# sparkfun-samd21-pro-breakout.net
KiCad netlist of a schematic drawn in EAGLE
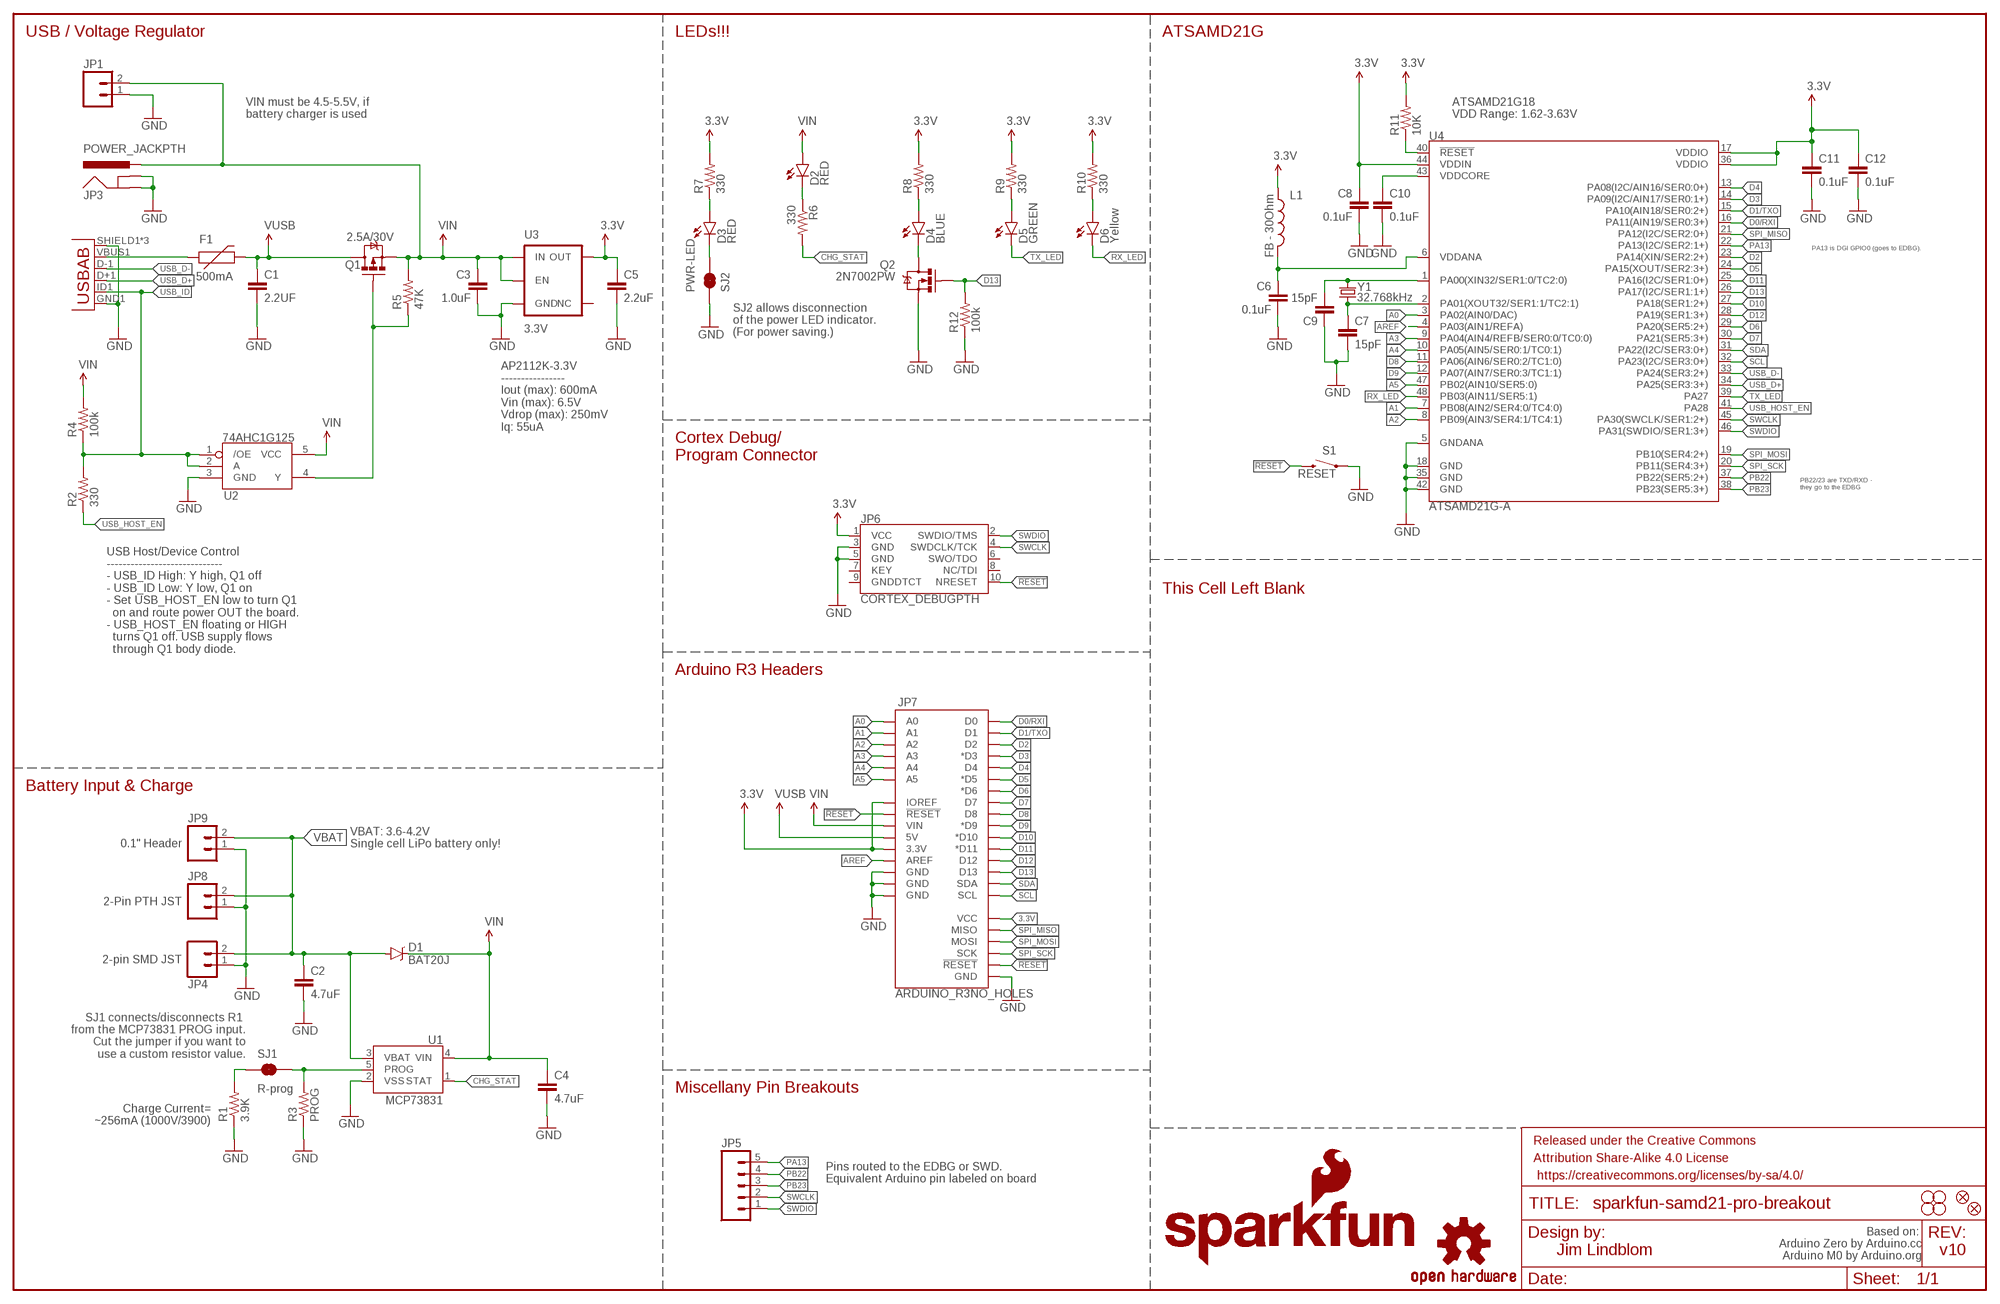
[diagram p0: schematic, sheet 1]

(export (version "E")
  (design (tool "Eeschema 10.0.6"))
  (components
    (comp (ref "C1")
      (value "2.2UF")
      (footprint "eagle-import:1206")
      (libsource (lib "eagle-import") (part "2.2UF50V10%(1206)"))
    )
    (comp (ref "C2")
      (value "4.7uF")
      (footprint "eagle-import:0603-CAP")
      (libsource (lib "eagle-import") (part "4.7UF-6.3V-10%(0603)0603"))
    )
    (comp (ref "C3")
      (value "1.0uF")
      (footprint "eagle-import:0805-CAP")
      (libsource (lib "eagle-import") (part "1.0UF-25V-+80/-20(0805){dblquote}"))
    )
    (comp (ref "C4")
      (value "4.7uF")
      (footprint "eagle-import:0603-CAP")
      (libsource (lib "eagle-import") (part "4.7UF-6.3V-10%(0603)0603"))
    )
    (comp (ref "C5")
      (value "2.2uF")
      (footprint "eagle-import:0603-CAP")
      (libsource (lib "eagle-import") (part "2.2UF-10V-20%(0603)"))
    )
    (comp (ref "C6")
      (value "0.1uF")
      (footprint "eagle-import:0603-CAP")
      (libsource (lib "eagle-import") (part "0.1UF-25V(+80/-20%)(0603)"))
    )
    (comp (ref "C7")
      (value "15pF")
      (footprint "eagle-import:0603-CAP")
      (libsource (lib "eagle-import") (part "15PF-50V-5%(0603)"))
    )
    (comp (ref "C8")
      (value "0.1uF")
      (footprint "eagle-import:0603-CAP")
      (libsource (lib "eagle-import") (part "0.1UF-25V(+80/-20%)(0603)"))
    )
    (comp (ref "C9")
      (value "15pF")
      (footprint "eagle-import:0603-CAP")
      (libsource (lib "eagle-import") (part "15PF-50V-5%(0603)"))
    )
    (comp (ref "C10")
      (value "0.1uF")
      (footprint "eagle-import:0603-CAP")
      (libsource (lib "eagle-import") (part "0.1UF-25V(+80/-20%)(0603)"))
    )
    (comp (ref "C11")
      (value "0.1uF")
      (footprint "eagle-import:0603-CAP")
      (libsource (lib "eagle-import") (part "0.1UF-25V(+80/-20%)(0603)"))
    )
    (comp (ref "C12")
      (value "0.1uF")
      (footprint "eagle-import:0603-CAP")
      (libsource (lib "eagle-import") (part "0.1UF-25V(+80/-20%)(0603)"))
    )
    (comp (ref "D1")
      (value "BAT20J")
      (footprint "eagle-import:SOD-323")
      (libsource (lib "eagle-import") (part "DIODE-SCHOTTKY-BAT20J"))
    )
    (comp (ref "D2")
      (value "RED")
      (footprint "eagle-import:LED-0603")
      (libsource (lib "eagle-import") (part "LED-RED0603"))
    )
    (comp (ref "D3")
      (value "RED")
      (footprint "eagle-import:LED-0603")
      (libsource (lib "eagle-import") (part "LED-RED0603"))
    )
    (comp (ref "D4")
      (value "BLUE")
      (footprint "eagle-import:LED-0603")
      (libsource (lib "eagle-import") (part "LED-BLUE0603"))
    )
    (comp (ref "D5")
      (value "GREEN")
      (footprint "eagle-import:LED-0603")
      (libsource (lib "eagle-import") (part "LED-GREEN0603"))
    )
    (comp (ref "D6")
      (value "Yellow")
      (footprint "eagle-import:LED-0603")
      (libsource (lib "eagle-import") (part "LED-YELLOW0603"))
    )
    (comp (ref "F1")
      (value "500mA")
      (footprint "eagle-import:PTC-1206")
      (libsource (lib "eagle-import") (part "PTCSMD"))
    )
    (comp (ref "FID1")
      (value "FIDUCIAL1X2")
      (footprint "eagle-import:FIDUCIAL-1X2")
      (libsource (lib "eagle-import") (part "FIDUCIAL1X2"))
    )
    (comp (ref "FID2")
      (value "FIDUCIAL1X2")
      (footprint "eagle-import:FIDUCIAL-1X2")
      (libsource (lib "eagle-import") (part "FIDUCIAL1X2"))
    )
    (comp (ref "FRAME1")
      (value "FRAME-LEDGER")
      (footprint "eagle-import:CREATIVE_COMMONS")
      (libsource (lib "eagle-import") (part "FRAME-LEDGER"))
    )
    (comp (ref "JP1")
      (value "M02PTH")
      (footprint "eagle-import:1X02")
      (libsource (lib "eagle-import") (part "M02PTH"))
    )
    (comp (ref "JP2")
      (value "USB-ABCONN-11794")
      (footprint "eagle-import:USB-AB-MICRO-SMD_V03")
      (libsource (lib "eagle-import") (part "USB-ABCONN-11794"))
    )
    (comp (ref "JP3")
      (value "POWER_JACKPTH")
      (footprint "eagle-import:POWER_JACK_PTH")
      (libsource (lib "eagle-import") (part "POWER_JACKPTH"))
    )
    (comp (ref "JP4")
      (value "M02-JST-2MM-SMT")
      (footprint "eagle-import:JST-2-SMD")
      (libsource (lib "eagle-import") (part "M02-JST-2MM-SMT"))
    )
    (comp (ref "JP5")
      (value "M05NO_SILK")
      (footprint "eagle-import:1X05_NO_SILK")
      (libsource (lib "eagle-import") (part "M05NO_SILK"))
    )
    (comp (ref "JP6")
      (value "CORTEX_DEBUGPTH")
      (footprint "eagle-import:2X5-PTH-1.27MM")
      (libsource (lib "eagle-import") (part "CORTEX_DEBUGPTH"))
    )
    (comp (ref "JP7")
      (value "ARDUINO_R3NO_HOLES")
      (footprint "eagle-import:ARDUINO_R3_NO_HOLES")
      (libsource (lib "eagle-import") (part "ARDUINO_R3NO_HOLES"))
    )
    (comp (ref "JP8")
      (value "M02-JST-2-PTH-NO_SILK")
      (footprint "eagle-import:JST-2-PTH-NS")
      (libsource (lib "eagle-import") (part "M02-JST-2-PTH-NO_SILK"))
    )
    (comp (ref "JP9")
      (value "M021X02_NO_SILK")
      (footprint "eagle-import:1X02_NO_SILK")
      (libsource (lib "eagle-import") (part "M021X02_NO_SILK"))
    )
    (comp (ref "L1")
      (value "FB - 30Ohm")
      (footprint "eagle-import:0603")
      (libsource (lib "eagle-import") (part "INDUCTOR0603"))
    )
    (comp (ref "LOGO1")
      (value "SFE_LOGO_NAME_FLAME.2_INCH")
      (footprint "eagle-import:SFE_LOGO_NAME_FLAME_.2")
      (libsource (lib "eagle-import") (part "SFE_LOGO_NAME_FLAME.2_INCH"))
    )
    (comp (ref "LOGO2")
      (value "SFE_LOGO_NAME_FLAME.4_INCH")
      (footprint "eagle-import:SFE_LOGO_NAME_FLAME_.4")
      (libsource (lib "eagle-import") (part "SFE_LOGO_NAME_FLAME.4_INCH"))
    )
    (comp (ref "LOGO3")
      (value "OSHW-LOGOS")
      (footprint "eagle-import:OSHW-LOGO-S")
      (libsource (lib "eagle-import") (part "OSHW-LOGOS"))
    )
    (comp (ref "LOGO4")
      (value "OSHW-LOGOL")
      (footprint "eagle-import:OSHW-LOGO-L")
      (libsource (lib "eagle-import") (part "OSHW-LOGOL"))
    )
    (comp (ref "Q1")
      (value "2.5A/30V")
      (footprint "eagle-import:SOT23-3")
      (libsource (lib "eagle-import") (part "MOSFET-PCHANNELDMG2307L"))
    )
    (comp (ref "Q2")
      (value "2N7002PW")
      (footprint "eagle-import:SOT323")
      (libsource (lib "eagle-import") (part "MOSFET-NCHANNEL2N7002PW"))
    )
    (comp (ref "R1")
      (value "3.9K")
      (footprint "eagle-import:0603")
      (libsource (lib "eagle-import") (part "3.9KOHM1/10W1%(0603)"))
    )
    (comp (ref "R2")
      (value "330")
      (footprint "eagle-import:0603-RES")
      (libsource (lib "eagle-import") (part "330OHM1/10W1%(0603)"))
    )
    (comp (ref "R3")
      (value "PROG")
      (footprint "eagle-import:1_6W-RES")
      (libsource (lib "eagle-import") (part "RESISTORPTH-1/6W"))
    )
    (comp (ref "R4")
      (value "100k")
      (footprint "eagle-import:0603-RES")
      (libsource (lib "eagle-import") (part "100KOHM-1/10W-1%(0603)"))
    )
    (comp (ref "R5")
      (value "47K")
      (footprint "eagle-import:0603-RES")
      (libsource (lib "eagle-import") (part "47KOHM1/10W1%(0603)"))
    )
    (comp (ref "R6")
      (value "330")
      (footprint "eagle-import:0603-RES")
      (libsource (lib "eagle-import") (part "330OHM1/10W1%(0603)"))
    )
    (comp (ref "R7")
      (value "330")
      (footprint "eagle-import:0603-RES")
      (libsource (lib "eagle-import") (part "330OHM1/10W1%(0603)"))
    )
    (comp (ref "R8")
      (value "330")
      (footprint "eagle-import:0603-RES")
      (libsource (lib "eagle-import") (part "330OHM1/10W1%(0603)"))
    )
    (comp (ref "R9")
      (value "330")
      (footprint "eagle-import:0603-RES")
      (libsource (lib "eagle-import") (part "330OHM1/10W1%(0603)"))
    )
    (comp (ref "R10")
      (value "330")
      (footprint "eagle-import:0603-RES")
      (libsource (lib "eagle-import") (part "330OHM1/10W1%(0603)"))
    )
    (comp (ref "R11")
      (value "10K")
      (footprint "eagle-import:0603-RES")
      (libsource (lib "eagle-import") (part "10KOHM-1/10W-1%(0603)0603"))
    )
    (comp (ref "R12")
      (value "100k")
      (footprint "eagle-import:0603-RES")
      (libsource (lib "eagle-import") (part "100KOHM-1/10W-1%(0603)"))
    )
    (comp (ref "S1")
      (value "RESET")
      (footprint "eagle-import:TACTILE-SWITCH-SMD")
      (libsource (lib "eagle-import") (part "SWITCH-MOMENTARY-2SMD"))
    )
    (comp (ref "SJ1")
      (value "R-prog")
      (footprint "eagle-import:PAD-JUMPER-2-NC_BY_TRACE_YES_SILK")
      (libsource (lib "eagle-import") (part "JUMPER-PAD-2-NC_BY_TRACE"))
    )
    (comp (ref "SJ2")
      (value "PWR-LED")
      (footprint "eagle-import:PAD-JUMPER-2-NC_BY_TRACE_NO_SILK")
      (libsource (lib "eagle-import") (part "JUMPER-PAD-2-NC_BY_TRACENO_SILK"))
    )
    (comp (ref "STANDOFF1")
      (value "STAND-OFF")
      (footprint "eagle-import:STAND-OFF")
      (libsource (lib "eagle-import") (part "STAND-OFF"))
    )
    (comp (ref "STANDOFF2")
      (value "STAND-OFF")
      (footprint "eagle-import:STAND-OFF")
      (libsource (lib "eagle-import") (part "STAND-OFF"))
    )
    (comp (ref "STANDOFF3")
      (value "STAND-OFF")
      (footprint "eagle-import:STAND-OFF")
      (libsource (lib "eagle-import") (part "STAND-OFF"))
    )
    (comp (ref "STANDOFF4")
      (value "STAND-OFF")
      (footprint "eagle-import:STAND-OFF")
      (libsource (lib "eagle-import") (part "STAND-OFF"))
    )
    (comp (ref "U1")
      (value "MCP73831")
      (footprint "eagle-import:SOT23-5")
      (libsource (lib "eagle-import") (part "MCP73831"))
    )
    (comp (ref "U2")
      (value "74AHC1G125")
      (footprint "eagle-import:SOT23-5")
      (libsource (lib "eagle-import") (part "74AHC1G125"))
    )
    (comp (ref "U3")
      (value "3.3V")
      (footprint "eagle-import:SOT23-5")
      (libsource (lib "eagle-import") (part "V_REG_AP2112K-3.3V"))
    )
    (comp (ref "U4")
      (value "ATSAMD21G-A")
      (footprint "eagle-import:TQFP-48")
      (libsource (lib "eagle-import") (part "ATSAMD21G-A"))
    )
    (comp (ref "Y1")
      (value "32.768kHz")
      (footprint "eagle-import:CRYSTAL-SMD-3.2X1.5MM")
      (libsource (lib "eagle-import") (part "CRYSTAL3.2X1.5MM"))
    )
  )
  (nets
    (net (code "1") (name "/~{RESET}") (class "Default")
      (node (ref "JP6") (pin "10") (pinfunction "NRESET_10") (pintype "bidirectional"))
      (node (ref "JP7") (pin "RESET@1") (pinfunction "~{RESET}_RESET@1") (pintype "bidirectional"))
      (node (ref "JP7") (pin "RESET@2") (pinfunction "~{RESET}_RESET@2") (pintype "bidirectional"))
      (node (ref "R11") (pin "1") (pinfunction "1_1") (pintype "passive"))
      (node (ref "S1") (pin "3") (pinfunction "2_3") (pintype "passive"))
      (node (ref "U4") (pin "40") (pinfunction "~{RESET}_40") (pintype "bidirectional"))
    )
    (net (code "2") (name "3.3V") (class "Default")
      (node (ref "C11") (pin "1") (pinfunction "1_1") (pintype "passive"))
      (node (ref "C12") (pin "1") (pinfunction "1_1") (pintype "passive"))
      (node (ref "C5") (pin "1") (pinfunction "1_1") (pintype "passive"))
      (node (ref "C8") (pin "1") (pinfunction "1_1") (pintype "passive"))
      (node (ref "JP6") (pin "1") (pinfunction "VCC_1") (pintype "bidirectional"))
      (node (ref "JP7") (pin "3.3V") (pinfunction "3.3V_3.3V") (pintype "bidirectional"))
      (node (ref "JP7") (pin "IOREF") (pinfunction "IOREF_IOREF") (pintype "bidirectional"))
      (node (ref "JP7") (pin "VCC") (pinfunction "VCC_VCC") (pintype "bidirectional"))
      (node (ref "L1") (pin "1") (pinfunction "1_1") (pintype "passive"))
      (node (ref "R10") (pin "2") (pinfunction "2_2") (pintype "passive"))
      (node (ref "R11") (pin "2") (pinfunction "2_2") (pintype "passive"))
      (node (ref "R7") (pin "2") (pinfunction "2_2") (pintype "passive"))
      (node (ref "R8") (pin "2") (pinfunction "2_2") (pintype "passive"))
      (node (ref "R9") (pin "2") (pinfunction "2_2") (pintype "passive"))
      (node (ref "U3") (pin "5") (pinfunction "OUT_5") (pintype "passive"))
      (node (ref "U4") (pin "17") (pinfunction "VDDIO_17") (pintype "bidirectional"))
      (node (ref "U4") (pin "36") (pinfunction "VDDIO_36") (pintype "bidirectional"))
      (node (ref "U4") (pin "44") (pinfunction "VDDIN_44") (pintype "bidirectional"))
    )
    (net (code "3") (name "A0") (class "Default")
      (node (ref "JP7") (pin "A0") (pinfunction "A0_A0") (pintype "bidirectional"))
      (node (ref "U4") (pin "3") (pinfunction "PA02(AIN0/DAC)_3") (pintype "bidirectional"))
    )
    (net (code "4") (name "A1") (class "Default")
      (node (ref "JP7") (pin "A1") (pinfunction "A1_A1") (pintype "bidirectional"))
      (node (ref "U4") (pin "7") (pinfunction "PB08(AIN2/SER4:0/TC4:0)_7") (pintype "bidirectional"))
    )
    (net (code "5") (name "A2") (class "Default")
      (node (ref "JP7") (pin "A2") (pinfunction "A2_A2") (pintype "bidirectional"))
      (node (ref "U4") (pin "8") (pinfunction "PB09(AIN3/SER4:1/TC4:1)_8") (pintype "bidirectional"))
    )
    (net (code "6") (name "A3") (class "Default")
      (node (ref "JP7") (pin "A3") (pinfunction "A3_A3") (pintype "bidirectional"))
      (node (ref "U4") (pin "9") (pinfunction "PA04(AIN4/REFB/SER0:0/TC0:0)_9") (pintype "bidirectional"))
    )
    (net (code "7") (name "A4") (class "Default")
      (node (ref "JP7") (pin "A4") (pinfunction "A4_A4") (pintype "bidirectional"))
      (node (ref "U4") (pin "10") (pinfunction "PA05(AIN5/SER0:1/TC0:1)_10") (pintype "bidirectional"))
    )
    (net (code "8") (name "A5") (class "Default")
      (node (ref "JP7") (pin "A5") (pinfunction "A5_A5") (pintype "bidirectional"))
      (node (ref "U4") (pin "47") (pinfunction "PB02(AIN10/SER5:0)_47") (pintype "bidirectional"))
    )
    (net (code "9") (name "AREF") (class "Default")
      (node (ref "JP7") (pin "AREF") (pinfunction "AREF_AREF") (pintype "bidirectional"))
      (node (ref "U4") (pin "4") (pinfunction "PA03(AIN1/REFA)_4") (pintype "bidirectional"))
    )
    (net (code "10") (name "CHG_STAT") (class "Default")
      (node (ref "R6") (pin "2") (pinfunction "2_2") (pintype "passive"))
      (node (ref "U1") (pin "1") (pinfunction "STAT_1") (pintype "output"))
    )
    (net (code "11") (name "D0{slash}RXI") (class "Default")
      (node (ref "JP7") (pin "D0") (pinfunction "D0_D0") (pintype "bidirectional"))
      (node (ref "U4") (pin "16") (pinfunction "PA11(AIN19/SER0:3+)_16") (pintype "bidirectional"))
    )
    (net (code "12") (name "D1{slash}TXO") (class "Default")
      (node (ref "JP7") (pin "D1") (pinfunction "D1_D1") (pintype "bidirectional"))
      (node (ref "U4") (pin "15") (pinfunction "PA10(AIN18/SER0:2+)_15") (pintype "bidirectional"))
    )
    (net (code "13") (name "D2") (class "Default")
      (node (ref "JP7") (pin "D2") (pinfunction "D2_D2") (pintype "bidirectional"))
      (node (ref "U4") (pin "23") (pinfunction "PA14(XIN/SER2:2+)_23") (pintype "bidirectional"))
    )
    (net (code "14") (name "D3") (class "Default")
      (node (ref "JP7") (pin "D3") (pinfunction "*D3_D3") (pintype "bidirectional"))
      (node (ref "U4") (pin "14") (pinfunction "PA09(I2C/AIN17/SER0:1+)_14") (pintype "bidirectional"))
    )
    (net (code "15") (name "D4") (class "Default")
      (node (ref "JP7") (pin "D4") (pinfunction "D4_D4") (pintype "bidirectional"))
      (node (ref "U4") (pin "13") (pinfunction "PA08(I2C/AIN16/SER0:0+)_13") (pintype "bidirectional"))
    )
    (net (code "16") (name "D5") (class "Default")
      (node (ref "JP7") (pin "D5") (pinfunction "*D5_D5") (pintype "bidirectional"))
      (node (ref "U4") (pin "24") (pinfunction "PA15(XOUT/SER2:3+)_24") (pintype "bidirectional"))
    )
    (net (code "17") (name "D6") (class "Default")
      (node (ref "JP7") (pin "D6") (pinfunction "*D6_D6") (pintype "bidirectional"))
      (node (ref "U4") (pin "29") (pinfunction "PA20(SER5:2+)_29") (pintype "bidirectional"))
    )
    (net (code "18") (name "D7") (class "Default")
      (node (ref "JP7") (pin "D7") (pinfunction "D7_D7") (pintype "bidirectional"))
      (node (ref "U4") (pin "30") (pinfunction "PA21(SER5:3+)_30") (pintype "bidirectional"))
    )
    (net (code "19") (name "D8") (class "Default")
      (node (ref "JP7") (pin "D8") (pinfunction "D8_D8") (pintype "bidirectional"))
      (node (ref "U4") (pin "11") (pinfunction "PA06(AIN6/SER0:2/TC1:0)_11") (pintype "bidirectional"))
    )
    (net (code "20") (name "D9") (class "Default")
      (node (ref "JP7") (pin "D9") (pinfunction "*D9_D9") (pintype "bidirectional"))
      (node (ref "U4") (pin "12") (pinfunction "PA07(AIN7/SER0:3/TC1:1)_12") (pintype "bidirectional"))
    )
    (net (code "21") (name "D10") (class "Default")
      (node (ref "JP7") (pin "D10") (pinfunction "*D10_D10") (pintype "bidirectional"))
      (node (ref "U4") (pin "27") (pinfunction "PA18(SER1:2+)_27") (pintype "bidirectional"))
    )
    (net (code "22") (name "D11") (class "Default")
      (node (ref "JP7") (pin "D11") (pinfunction "*D11_D11") (pintype "bidirectional"))
      (node (ref "U4") (pin "25") (pinfunction "PA16(I2C/SER1:0+)_25") (pintype "bidirectional"))
    )
    (net (code "23") (name "D12") (class "Default")
      (node (ref "JP7") (pin "D12") (pinfunction "D12_D12") (pintype "bidirectional"))
      (node (ref "U4") (pin "28") (pinfunction "PA19(SER1:3+)_28") (pintype "bidirectional"))
    )
    (net (code "24") (name "D13") (class "Default")
      (node (ref "JP7") (pin "D13") (pinfunction "D13_D13") (pintype "bidirectional"))
      (node (ref "Q2") (pin "1") (pinfunction "G_1") (pintype "passive"))
      (node (ref "R12") (pin "2") (pinfunction "2_2") (pintype "passive"))
      (node (ref "U4") (pin "26") (pinfunction "PA17(I2C/SER1:1+)_26") (pintype "bidirectional"))
    )
    (net (code "25") (name "GND") (class "Default")
      (node (ref "C1") (pin "2") (pinfunction "2_2") (pintype "passive"))
      (node (ref "C10") (pin "2") (pinfunction "2_2") (pintype "passive"))
      (node (ref "C11") (pin "2") (pinfunction "2_2") (pintype "passive"))
      (node (ref "C12") (pin "2") (pinfunction "2_2") (pintype "passive"))
      (node (ref "C2") (pin "2") (pinfunction "2_2") (pintype "passive"))
      (node (ref "C3") (pin "2") (pinfunction "2_2") (pintype "passive"))
      (node (ref "C4") (pin "2") (pinfunction "2_2") (pintype "passive"))
      (node (ref "C5") (pin "2") (pinfunction "2_2") (pintype "passive"))
      (node (ref "C6") (pin "2") (pinfunction "2_2") (pintype "passive"))
      (node (ref "C7") (pin "2") (pinfunction "2_2") (pintype "passive"))
      (node (ref "C8") (pin "2") (pinfunction "2_2") (pintype "passive"))
      (node (ref "C9") (pin "1") (pinfunction "1_1") (pintype "passive"))
      (node (ref "JP1") (pin "1") (pinfunction "1_1") (pintype "passive"))
      (node (ref "JP2") (pin "GND1") (pinfunction "GND_GND1") (pintype "bidirectional"))
      (node (ref "JP2") (pin "SHIELD1") (pinfunction "SHIELD_SHIELD1") (pintype "bidirectional"))
      (node (ref "JP2") (pin "SHIELD2") (pinfunction "SHIELD_SHIELD2") (pintype "bidirectional"))
      (node (ref "JP2") (pin "SHIELD3") (pinfunction "SHIELD_SHIELD3") (pintype "bidirectional"))
      (node (ref "JP3") (pin "GND") (pinfunction "GND_GND") (pintype "bidirectional"))
      (node (ref "JP3") (pin "GNDBREAK") (pinfunction "GNDBREAK_GNDBREAK") (pintype "bidirectional"))
      (node (ref "JP4") (pin "1") (pinfunction "2_1") (pintype "passive"))
      (node (ref "JP6") (pin "3") (pinfunction "GND_3") (pintype "bidirectional"))
      (node (ref "JP6") (pin "5") (pinfunction "GND_5") (pintype "bidirectional"))
      (node (ref "JP7") (pin "GND@1") (pinfunction "GND_GND@1") (pintype "bidirectional"))
      (node (ref "JP7") (pin "GND@2") (pinfunction "GND_GND@2") (pintype "bidirectional"))
      (node (ref "JP7") (pin "GND@3") (pinfunction "GND_GND@3") (pintype "bidirectional"))
      (node (ref "JP7") (pin "GND@4") (pinfunction "GND_GND@4") (pintype "bidirectional"))
      (node (ref "JP8") (pin "1") (pinfunction "1_1") (pintype "passive"))
      (node (ref "JP9") (pin "1") (pinfunction "1_1") (pintype "passive"))
      (node (ref "Q2") (pin "2") (pinfunction "S_2") (pintype "passive"))
      (node (ref "R1") (pin "1") (pinfunction "1_1") (pintype "passive"))
      (node (ref "R12") (pin "1") (pinfunction "1_1") (pintype "passive"))
      (node (ref "R3") (pin "1") (pinfunction "1_1") (pintype "passive"))
      (node (ref "S1") (pin "1") (pinfunction "1_1") (pintype "passive"))
      (node (ref "SJ2") (pin "1") (pinfunction "1_1") (pintype "passive"))
      (node (ref "U1") (pin "2") (pinfunction "VSS_2") (pintype "power_in"))
      (node (ref "U2") (pin "3") (pinfunction "GND_3") (pintype "bidirectional"))
      (node (ref "U3") (pin "2") (pinfunction "GND_2") (pintype "input"))
      (node (ref "U4") (pin "18") (pinfunction "GND_18") (pintype "bidirectional"))
      (node (ref "U4") (pin "35") (pinfunction "GND_35") (pintype "bidirectional"))
      (node (ref "U4") (pin "42") (pinfunction "GND_42") (pintype "bidirectional"))
      (node (ref "U4") (pin "5") (pinfunction "GNDANA_5") (pintype "bidirectional"))
    )
    (net (code "26") (name "Net-(D2-PadC)") (class "Default")
      (node (ref "D2") (pin "C") (pinfunction "C_C") (pintype "passive"))
      (node (ref "R6") (pin "1") (pinfunction "1_1") (pintype "passive"))
    )
    (net (code "27") (name "Net-(D3-PadA)") (class "Default")
      (node (ref "D3") (pin "A") (pinfunction "A_A") (pintype "passive"))
      (node (ref "R7") (pin "1") (pinfunction "1_1") (pintype "passive"))
    )
    (net (code "28") (name "Net-(D3-PadC)") (class "Default")
      (node (ref "D3") (pin "C") (pinfunction "C_C") (pintype "passive"))
      (node (ref "SJ2") (pin "2") (pinfunction "2_2") (pintype "passive"))
    )
    (net (code "29") (name "Net-(D4-PadA)") (class "Default")
      (node (ref "D4") (pin "A") (pinfunction "A_A") (pintype "passive"))
      (node (ref "R8") (pin "1") (pinfunction "1_1") (pintype "passive"))
    )
    (net (code "30") (name "Net-(D5-PadA)") (class "Default")
      (node (ref "D5") (pin "A") (pinfunction "A_A") (pintype "passive"))
      (node (ref "R9") (pin "1") (pinfunction "1_1") (pintype "passive"))
    )
    (net (code "31") (name "Net-(D6-PadA)") (class "Default")
      (node (ref "D6") (pin "A") (pinfunction "A_A") (pintype "passive"))
      (node (ref "R10") (pin "1") (pinfunction "1_1") (pintype "passive"))
    )
    (net (code "32") (name "Net-(JP2-VBUS)") (class "Default")
      (node (ref "F1") (pin "1") (pinfunction "1_1") (pintype "bidirectional"))
      (node (ref "JP2") (pin "VBUS1") (pinfunction "VBUS_VBUS1") (pintype "bidirectional"))
    )
    (net (code "33") (name "Net-(Q1-G)") (class "Default")
      (node (ref "Q1") (pin "1") (pinfunction "G_1") (pintype "passive"))
      (node (ref "R5") (pin "1") (pinfunction "1_1") (pintype "passive"))
      (node (ref "U2") (pin "4") (pinfunction "Y_4") (pintype "bidirectional"))
    )
    (net (code "34") (name "Net-(Q2-D)") (class "Default")
      (node (ref "D4") (pin "C") (pinfunction "C_C") (pintype "passive"))
      (node (ref "Q2") (pin "3") (pinfunction "D_3") (pintype "passive"))
    )
    (net (code "35") (name "Net-(R1-Pad2)") (class "Default")
      (node (ref "R1") (pin "2") (pinfunction "2_2") (pintype "passive"))
      (node (ref "SJ1") (pin "1") (pinfunction "1_1") (pintype "passive"))
    )
    (net (code "36") (name "Net-(U1-PROG)") (class "Default")
      (node (ref "R3") (pin "2") (pinfunction "2_2") (pintype "passive"))
      (node (ref "SJ1") (pin "2") (pinfunction "2_2") (pintype "passive"))
      (node (ref "U1") (pin "5") (pinfunction "PROG_5") (pintype "input"))
    )
    (net (code "37") (name "Net-(U4-PA00(XIN32{slash}SER1:0{slash}TC2:0))") (class "Default")
      (node (ref "C9") (pin "2") (pinfunction "2_2") (pintype "passive"))
      (node (ref "U4") (pin "1") (pinfunction "PA00(XIN32/SER1:0/TC2:0)_1") (pintype "bidirectional"))
      (node (ref "Y1") (pin "P$2") (pinfunction "2_P$2") (pintype "passive"))
    )
    (net (code "38") (name "Net-(U4-PA01(XOUT32{slash}SER1:1{slash}TC2:1))") (class "Default")
      (node (ref "C7") (pin "1") (pinfunction "1_1") (pintype "passive"))
      (node (ref "U4") (pin "2") (pinfunction "PA01(XOUT32/SER1:1/TC2:1)_2") (pintype "bidirectional"))
      (node (ref "Y1") (pin "P$1") (pinfunction "1_P$1") (pintype "passive"))
    )
    (net (code "39") (name "Net-(U4-VDDANA)") (class "Default")
      (node (ref "C6") (pin "1") (pinfunction "1_1") (pintype "passive"))
      (node (ref "L1") (pin "2") (pinfunction "2_2") (pintype "passive"))
      (node (ref "U4") (pin "6") (pinfunction "VDDANA_6") (pintype "bidirectional"))
    )
    (net (code "40") (name "Net-(U4-VDDCORE)") (class "Default")
      (node (ref "C10") (pin "1") (pinfunction "1_1") (pintype "passive"))
      (node (ref "U4") (pin "43") (pinfunction "VDDCORE_43") (pintype "bidirectional"))
    )
    (net (code "41") (name "PA13") (class "Default")
      (node (ref "JP5") (pin "5") (pinfunction "5_5") (pintype "passive"))
      (node (ref "U4") (pin "22") (pinfunction "PA13(I2C/SER2:1+)_22") (pintype "bidirectional"))
    )
    (net (code "42") (name "PB22") (class "Default")
      (node (ref "JP5") (pin "4") (pinfunction "4_4") (pintype "passive"))
      (node (ref "U4") (pin "37") (pinfunction "PB22(SER5:2+)_37") (pintype "bidirectional"))
    )
    (net (code "43") (name "PB23") (class "Default")
      (node (ref "JP5") (pin "3") (pinfunction "3_3") (pintype "passive"))
      (node (ref "U4") (pin "38") (pinfunction "PB23(SER5:3+)_38") (pintype "bidirectional"))
    )
    (net (code "44") (name "RX_LED") (class "Default")
      (node (ref "D6") (pin "C") (pinfunction "C_C") (pintype "passive"))
      (node (ref "U4") (pin "48") (pinfunction "PB03(AIN11/SER5:1)_48") (pintype "bidirectional"))
    )
    (net (code "45") (name "SCL") (class "Default")
      (node (ref "JP7") (pin "SCL") (pinfunction "SCL_SCL") (pintype "bidirectional"))
      (node (ref "U4") (pin "32") (pinfunction "PA23(I2C/SER3:0+)_32") (pintype "bidirectional"))
    )
    (net (code "46") (name "SDA") (class "Default")
      (node (ref "JP7") (pin "SDA") (pinfunction "SDA_SDA") (pintype "bidirectional"))
      (node (ref "U4") (pin "31") (pinfunction "PA22(I2C/SER3:0+)_31") (pintype "bidirectional"))
    )
    (net (code "47") (name "SPI_MISO") (class "Default")
      (node (ref "JP7") (pin "MISO") (pinfunction "MISO_MISO") (pintype "bidirectional"))
      (node (ref "U4") (pin "21") (pinfunction "PA12(I2C/SER2:0+)_21") (pintype "bidirectional"))
    )
    (net (code "48") (name "SPI_MOSI") (class "Default")
      (node (ref "JP7") (pin "MOSI") (pinfunction "MOSI_MOSI") (pintype "bidirectional"))
      (node (ref "U4") (pin "19") (pinfunction "PB10(SER4:2+)_19") (pintype "bidirectional"))
    )
    (net (code "49") (name "SPI_SCK") (class "Default")
      (node (ref "JP7") (pin "SCK") (pinfunction "SCK_SCK") (pintype "bidirectional"))
      (node (ref "U4") (pin "20") (pinfunction "PB11(SER4:3+)_20") (pintype "bidirectional"))
    )
    (net (code "50") (name "SWCLK") (class "Default")
      (node (ref "JP5") (pin "2") (pinfunction "2_2") (pintype "passive"))
      (node (ref "JP6") (pin "4") (pinfunction "SWDCLK/TCK_4") (pintype "bidirectional"))
      (node (ref "U4") (pin "45") (pinfunction "PA30(SWCLK/SER1:2+)_45") (pintype "bidirectional"))
    )
    (net (code "51") (name "SWDIO") (class "Default")
      (node (ref "JP5") (pin "1") (pinfunction "1_1") (pintype "passive"))
      (node (ref "JP6") (pin "2") (pinfunction "SWDIO/TMS_2") (pintype "bidirectional"))
      (node (ref "U4") (pin "46") (pinfunction "PA31(SWDIO/SER1:3+)_46") (pintype "bidirectional"))
    )
    (net (code "52") (name "TX_LED") (class "Default")
      (node (ref "D5") (pin "C") (pinfunction "C_C") (pintype "passive"))
      (node (ref "U4") (pin "39") (pinfunction "PA27_39") (pintype "bidirectional"))
    )
    (net (code "53") (name "USB_D+") (class "Default")
      (node (ref "JP2") (pin "D+1") (pinfunction "D+_D+1") (pintype "bidirectional"))
      (node (ref "U4") (pin "34") (pinfunction "PA25(SER3:3+)_34") (pintype "bidirectional"))
    )
    (net (code "54") (name "USB_D-") (class "Default")
      (node (ref "JP2") (pin "D-1") (pinfunction "D-_D-1") (pintype "bidirectional"))
      (node (ref "U4") (pin "33") (pinfunction "PA24(SER3:2+)_33") (pintype "bidirectional"))
    )
    (net (code "55") (name "USB_HOST_EN") (class "Default")
      (node (ref "R2") (pin "1") (pinfunction "1_1") (pintype "passive"))
      (node (ref "U4") (pin "41") (pinfunction "PA28_41") (pintype "bidirectional"))
    )
    (net (code "56") (name "USB_ID") (class "Default")
      (node (ref "JP2") (pin "ID1") (pinfunction "USBID_ID1") (pintype "bidirectional"))
      (node (ref "R2") (pin "2") (pinfunction "2_2") (pintype "passive"))
      (node (ref "R4") (pin "1") (pinfunction "1_1") (pintype "passive"))
      (node (ref "U2") (pin "1") (pinfunction "/OE_1") (pintype "bidirectional"))
      (node (ref "U2") (pin "2") (pinfunction "A_2") (pintype "bidirectional"))
    )
    (net (code "57") (name "VBAT") (class "Default")
      (node (ref "C2") (pin "1") (pinfunction "1_1") (pintype "passive"))
      (node (ref "D1") (pin "A") (pinfunction "A_A") (pintype "passive"))
      (node (ref "JP4") (pin "2") (pinfunction "1_2") (pintype "passive"))
      (node (ref "JP8") (pin "2") (pinfunction "2_2") (pintype "passive"))
      (node (ref "JP9") (pin "2") (pinfunction "2_2") (pintype "passive"))
      (node (ref "U1") (pin "3") (pinfunction "VBAT_3") (pintype "power_in"))
    )
    (net (code "58") (name "VIN") (class "Default")
      (node (ref "C3") (pin "1") (pinfunction "1_1") (pintype "passive"))
      (node (ref "C4") (pin "1") (pinfunction "1_1") (pintype "passive"))
      (node (ref "D1") (pin "C") (pinfunction "C_C") (pintype "passive"))
      (node (ref "D2") (pin "A") (pinfunction "A_A") (pintype "passive"))
      (node (ref "JP1") (pin "2") (pinfunction "2_2") (pintype "passive"))
      (node (ref "JP3") (pin "PWR") (pinfunction "PWR_PWR") (pintype "bidirectional"))
      (node (ref "JP7") (pin "VIN") (pinfunction "VIN_VIN") (pintype "bidirectional"))
      (node (ref "Q1") (pin "2") (pinfunction "S_2") (pintype "passive"))
      (node (ref "R4") (pin "2") (pinfunction "2_2") (pintype "passive"))
      (node (ref "R5") (pin "2") (pinfunction "2_2") (pintype "passive"))
      (node (ref "U1") (pin "4") (pinfunction "VIN_4") (pintype "power_in"))
      (node (ref "U2") (pin "5") (pinfunction "VCC_5") (pintype "bidirectional"))
      (node (ref "U3") (pin "1") (pinfunction "IN_1") (pintype "input"))
      (node (ref "U3") (pin "3") (pinfunction "EN_3") (pintype "input"))
    )
    (net (code "59") (name "VUSB") (class "Default")
      (node (ref "C1") (pin "1") (pinfunction "1_1") (pintype "passive"))
      (node (ref "F1") (pin "2") (pinfunction "2_2") (pintype "bidirectional"))
      (node (ref "JP7") (pin "5V") (pinfunction "5V_5V") (pintype "bidirectional"))
      (node (ref "Q1") (pin "3") (pinfunction "D_3") (pintype "passive"))
    )
    (net (code "60") (name "unconnected-(JP6-GNDDTCT-Pad9)") (class "Default")
      (node (ref "JP6") (pin "9") (pinfunction "GNDDTCT_9") (pintype "bidirectional"))
    )
    (net (code "61") (name "unconnected-(JP6-KEY-Pad7)") (class "Default")
      (node (ref "JP6") (pin "7") (pinfunction "KEY_7") (pintype "bidirectional"))
    )
    (net (code "62") (name "unconnected-(JP6-NC{slash}TDI-Pad8)") (class "Default")
      (node (ref "JP6") (pin "8") (pinfunction "NC/TDI_8") (pintype "bidirectional"))
    )
    (net (code "63") (name "unconnected-(JP6-SWO{slash}TDO-Pad6)") (class "Default")
      (node (ref "JP6") (pin "6") (pinfunction "SWO/TDO_6") (pintype "bidirectional"))
    )
    (net (code "64") (name "unconnected-(U3-NC-Pad4)") (class "Default")
      (node (ref "U3") (pin "4") (pinfunction "NC_4") (pintype "input"))
    )
  )
)
